# 70_Signalleuchten.net
KiCad netlist of a schematic drawn in Altium Designer
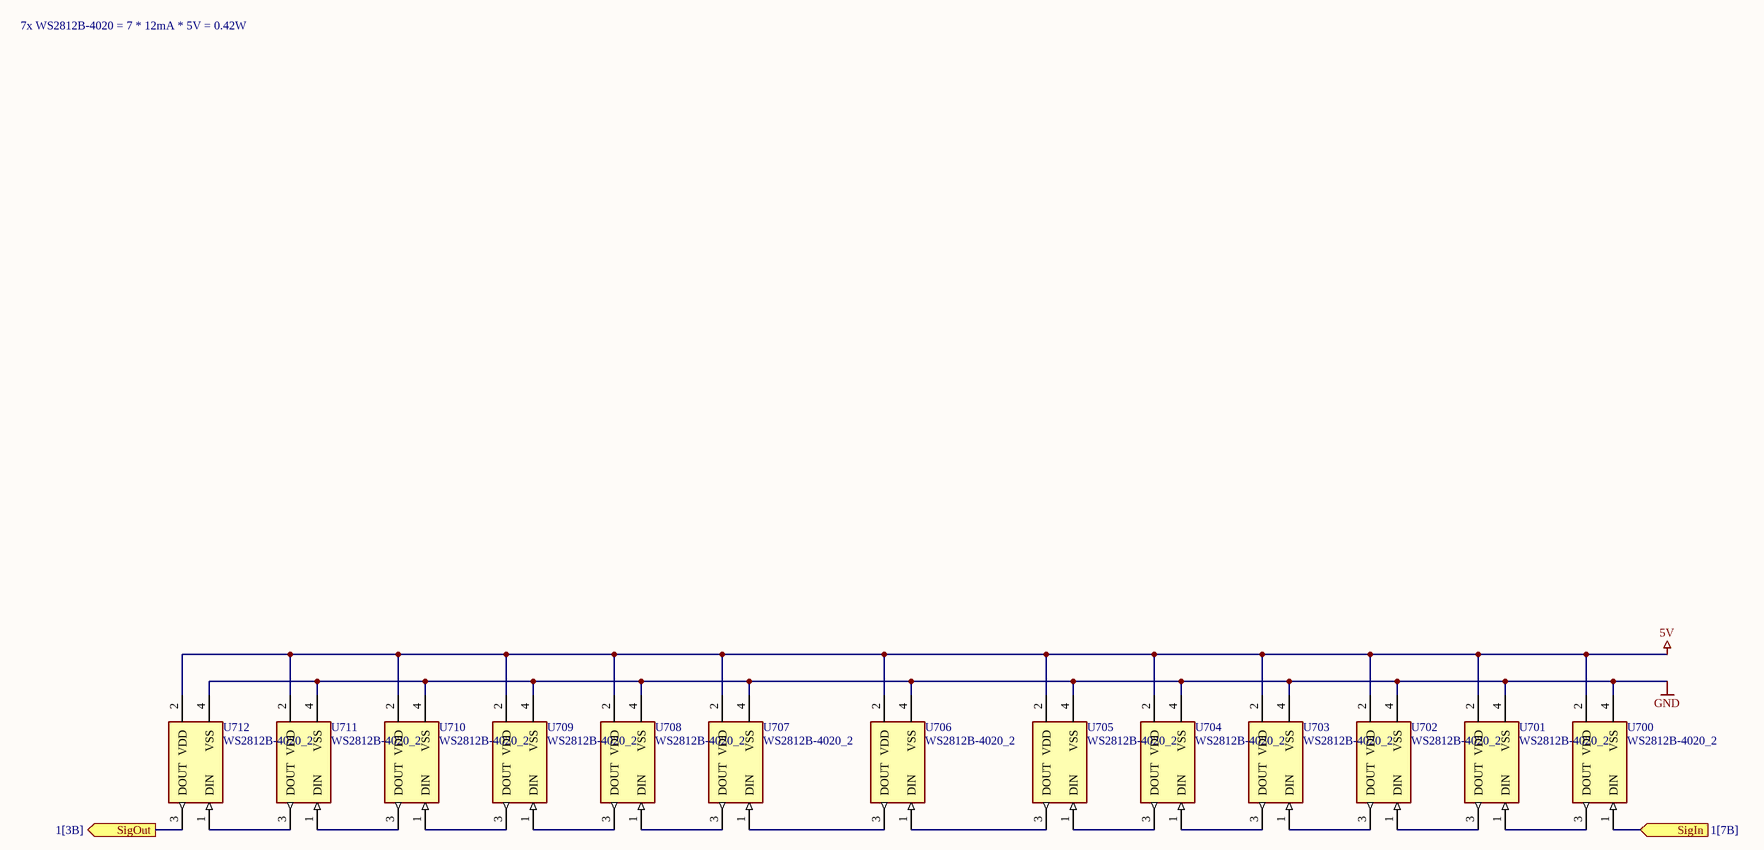
[diagram p0: 70_Signalleuchten.SchDoc]

(export (version "E")
  (design (tool "Eeschema 10.0.6"))
  (components
    (comp (ref "U700")
      (value "WS2812B-4020_2")
      (footprint "LED_WS2812B-4020")
      (description "12mA RGB SMD,2x4mm Light Emitting Diodes")
      (fields (field (name "MP") "WS2812B-4020") (field (name "MF") "Worldsemi"))
      (libsource (lib "AltiumLib_MILUTIN") (part "WS2812B-4020_2"))
    )
    (comp (ref "U701")
      (value "WS2812B-4020_2")
      (footprint "LED_WS2812B-4020")
      (description "12mA RGB SMD,2x4mm Light Emitting Diodes")
      (fields (field (name "MP") "WS2812B-4020") (field (name "MF") "Worldsemi"))
      (libsource (lib "AltiumLib_MILUTIN") (part "WS2812B-4020_2"))
    )
    (comp (ref "U702")
      (value "WS2812B-4020_2")
      (footprint "LED_WS2812B-4020")
      (description "12mA RGB SMD,2x4mm Light Emitting Diodes")
      (fields (field (name "MP") "WS2812B-4020") (field (name "MF") "Worldsemi"))
      (libsource (lib "AltiumLib_MILUTIN") (part "WS2812B-4020_2"))
    )
    (comp (ref "U703")
      (value "WS2812B-4020_2")
      (footprint "LED_WS2812B-4020")
      (description "12mA RGB SMD,2x4mm Light Emitting Diodes")
      (fields (field (name "MP") "WS2812B-4020") (field (name "MF") "Worldsemi"))
      (libsource (lib "AltiumLib_MILUTIN") (part "WS2812B-4020_2"))
    )
    (comp (ref "U704")
      (value "WS2812B-4020_2")
      (footprint "LED_WS2812B-4020")
      (description "12mA RGB SMD,2x4mm Light Emitting Diodes")
      (fields (field (name "MP") "WS2812B-4020") (field (name "MF") "Worldsemi"))
      (libsource (lib "AltiumLib_MILUTIN") (part "WS2812B-4020_2"))
    )
    (comp (ref "U705")
      (value "WS2812B-4020_2")
      (footprint "LED_WS2812B-4020")
      (description "12mA RGB SMD,2x4mm Light Emitting Diodes")
      (fields (field (name "MP") "WS2812B-4020") (field (name "MF") "Worldsemi"))
      (libsource (lib "AltiumLib_MILUTIN") (part "WS2812B-4020_2"))
    )
    (comp (ref "U706")
      (value "WS2812B-4020_2")
      (footprint "LED_WS2812B-4020")
      (description "12mA RGB SMD,2x4mm Light Emitting Diodes")
      (fields (field (name "MP") "WS2812B-4020") (field (name "MF") "Worldsemi"))
      (libsource (lib "AltiumLib_MILUTIN") (part "WS2812B-4020_2"))
    )
    (comp (ref "U707")
      (value "WS2812B-4020_2")
      (footprint "LED_WS2812B-4020")
      (description "12mA RGB SMD,2x4mm Light Emitting Diodes")
      (fields (field (name "MP") "WS2812B-4020") (field (name "MF") "Worldsemi"))
      (libsource (lib "AltiumLib_MILUTIN") (part "WS2812B-4020_2"))
    )
    (comp (ref "U708")
      (value "WS2812B-4020_2")
      (footprint "LED_WS2812B-4020")
      (description "12mA RGB SMD,2x4mm Light Emitting Diodes")
      (fields (field (name "MP") "WS2812B-4020") (field (name "MF") "Worldsemi"))
      (libsource (lib "AltiumLib_MILUTIN") (part "WS2812B-4020_2"))
    )
    (comp (ref "U709")
      (value "WS2812B-4020_2")
      (footprint "LED_WS2812B-4020")
      (description "12mA RGB SMD,2x4mm Light Emitting Diodes")
      (fields (field (name "MP") "WS2812B-4020") (field (name "MF") "Worldsemi"))
      (libsource (lib "AltiumLib_MILUTIN") (part "WS2812B-4020_2"))
    )
    (comp (ref "U710")
      (value "WS2812B-4020_2")
      (footprint "LED_WS2812B-4020")
      (description "12mA RGB SMD,2x4mm Light Emitting Diodes")
      (fields (field (name "MP") "WS2812B-4020") (field (name "MF") "Worldsemi"))
      (libsource (lib "AltiumLib_MILUTIN") (part "WS2812B-4020_2"))
    )
    (comp (ref "U711")
      (value "WS2812B-4020_2")
      (footprint "LED_WS2812B-4020")
      (description "12mA RGB SMD,2x4mm Light Emitting Diodes")
      (fields (field (name "MP") "WS2812B-4020") (field (name "MF") "Worldsemi"))
      (libsource (lib "AltiumLib_MILUTIN") (part "WS2812B-4020_2"))
    )
    (comp (ref "U712")
      (value "WS2812B-4020_2")
      (footprint "LED_WS2812B-4020")
      (description "12mA RGB SMD,2x4mm Light Emitting Diodes")
      (fields (field (name "MP") "WS2812B-4020") (field (name "MF") "Worldsemi"))
      (libsource (lib "AltiumLib_MILUTIN") (part "WS2812B-4020_2"))
    )
  )
  (nets
    (net (code "1") (name "/SigIn") (class "Default")
      (node (ref "U700") (pin "1") (pinfunction "DIN_1") (pintype "input"))
    )
    (net (code "2") (name "/SigOut") (class "Default")
      (node (ref "U712") (pin "3") (pinfunction "DOUT_3") (pintype "output"))
    )
    (net (code "3") (name "5V") (class "Default")
      (node (ref "U700") (pin "2") (pinfunction "VDD_2") (pintype "power_in"))
      (node (ref "U701") (pin "2") (pinfunction "VDD_2") (pintype "power_in"))
      (node (ref "U702") (pin "2") (pinfunction "VDD_2") (pintype "power_in"))
      (node (ref "U703") (pin "2") (pinfunction "VDD_2") (pintype "power_in"))
      (node (ref "U704") (pin "2") (pinfunction "VDD_2") (pintype "power_in"))
      (node (ref "U705") (pin "2") (pinfunction "VDD_2") (pintype "power_in"))
      (node (ref "U706") (pin "2") (pinfunction "VDD_2") (pintype "power_in"))
      (node (ref "U707") (pin "2") (pinfunction "VDD_2") (pintype "power_in"))
      (node (ref "U708") (pin "2") (pinfunction "VDD_2") (pintype "power_in"))
      (node (ref "U709") (pin "2") (pinfunction "VDD_2") (pintype "power_in"))
      (node (ref "U710") (pin "2") (pinfunction "VDD_2") (pintype "power_in"))
      (node (ref "U711") (pin "2") (pinfunction "VDD_2") (pintype "power_in"))
      (node (ref "U712") (pin "2") (pinfunction "VDD_2") (pintype "power_in"))
    )
    (net (code "4") (name "GND") (class "Default")
      (node (ref "U700") (pin "4") (pinfunction "VSS_4") (pintype "power_in"))
      (node (ref "U701") (pin "4") (pinfunction "VSS_4") (pintype "power_in"))
      (node (ref "U702") (pin "4") (pinfunction "VSS_4") (pintype "power_in"))
      (node (ref "U703") (pin "4") (pinfunction "VSS_4") (pintype "power_in"))
      (node (ref "U704") (pin "4") (pinfunction "VSS_4") (pintype "power_in"))
      (node (ref "U705") (pin "4") (pinfunction "VSS_4") (pintype "power_in"))
      (node (ref "U706") (pin "4") (pinfunction "VSS_4") (pintype "power_in"))
      (node (ref "U707") (pin "4") (pinfunction "VSS_4") (pintype "power_in"))
      (node (ref "U708") (pin "4") (pinfunction "VSS_4") (pintype "power_in"))
      (node (ref "U709") (pin "4") (pinfunction "VSS_4") (pintype "power_in"))
      (node (ref "U710") (pin "4") (pinfunction "VSS_4") (pintype "power_in"))
      (node (ref "U711") (pin "4") (pinfunction "VSS_4") (pintype "power_in"))
      (node (ref "U712") (pin "4") (pinfunction "VSS_4") (pintype "power_in"))
    )
    (net (code "5") (name "Net-(U700-DOUT)") (class "Default")
      (node (ref "U700") (pin "3") (pinfunction "DOUT_3") (pintype "output"))
      (node (ref "U701") (pin "1") (pinfunction "DIN_1") (pintype "input"))
    )
    (net (code "6") (name "Net-(U701-DOUT)") (class "Default")
      (node (ref "U701") (pin "3") (pinfunction "DOUT_3") (pintype "output"))
      (node (ref "U702") (pin "1") (pinfunction "DIN_1") (pintype "input"))
    )
    (net (code "7") (name "Net-(U702-DOUT)") (class "Default")
      (node (ref "U702") (pin "3") (pinfunction "DOUT_3") (pintype "output"))
      (node (ref "U703") (pin "1") (pinfunction "DIN_1") (pintype "input"))
    )
    (net (code "8") (name "Net-(U703-DOUT)") (class "Default")
      (node (ref "U703") (pin "3") (pinfunction "DOUT_3") (pintype "output"))
      (node (ref "U704") (pin "1") (pinfunction "DIN_1") (pintype "input"))
    )
    (net (code "9") (name "Net-(U704-DOUT)") (class "Default")
      (node (ref "U704") (pin "3") (pinfunction "DOUT_3") (pintype "output"))
      (node (ref "U705") (pin "1") (pinfunction "DIN_1") (pintype "input"))
    )
    (net (code "10") (name "Net-(U705-DOUT)") (class "Default")
      (node (ref "U705") (pin "3") (pinfunction "DOUT_3") (pintype "output"))
      (node (ref "U706") (pin "1") (pinfunction "DIN_1") (pintype "input"))
    )
    (net (code "11") (name "Net-(U706-DOUT)") (class "Default")
      (node (ref "U706") (pin "3") (pinfunction "DOUT_3") (pintype "output"))
      (node (ref "U707") (pin "1") (pinfunction "DIN_1") (pintype "input"))
    )
    (net (code "12") (name "Net-(U707-DOUT)") (class "Default")
      (node (ref "U707") (pin "3") (pinfunction "DOUT_3") (pintype "output"))
      (node (ref "U708") (pin "1") (pinfunction "DIN_1") (pintype "input"))
    )
    (net (code "13") (name "Net-(U708-DOUT)") (class "Default")
      (node (ref "U708") (pin "3") (pinfunction "DOUT_3") (pintype "output"))
      (node (ref "U709") (pin "1") (pinfunction "DIN_1") (pintype "input"))
    )
    (net (code "14") (name "Net-(U709-DOUT)") (class "Default")
      (node (ref "U709") (pin "3") (pinfunction "DOUT_3") (pintype "output"))
      (node (ref "U710") (pin "1") (pinfunction "DIN_1") (pintype "input"))
    )
    (net (code "15") (name "Net-(U710-DOUT)") (class "Default")
      (node (ref "U710") (pin "3") (pinfunction "DOUT_3") (pintype "output"))
      (node (ref "U711") (pin "1") (pinfunction "DIN_1") (pintype "input"))
    )
    (net (code "16") (name "Net-(U711-DOUT)") (class "Default")
      (node (ref "U711") (pin "3") (pinfunction "DOUT_3") (pintype "output"))
      (node (ref "U712") (pin "1") (pinfunction "DIN_1") (pintype "input"))
    )
  )
)
